# ultimatedrive1.net
KiCad netlist of a schematic drawn in EAGLE
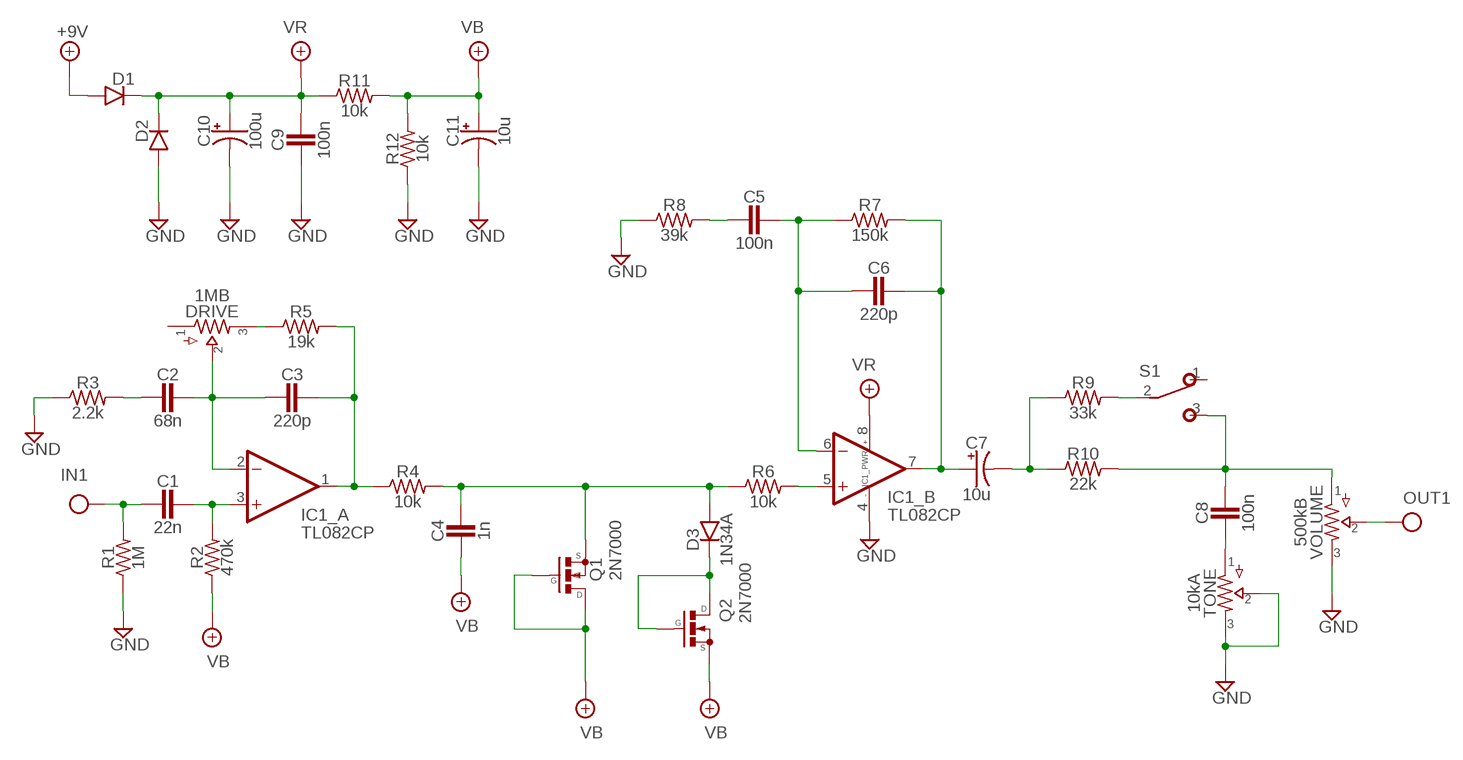
[diagram p0: schematic, sheet 1]

(export (version "E")
  (design (tool "Eeschema 10.0.6"))
  (components
    (comp (ref "C1")
      (value "22n")
      (footprint "eagle-import:BOX_SMALL")
      (libsource (lib "eagle-import") (part "CER/FILMBOX.1"))
    )
    (comp (ref "C2")
      (value "68n")
      (footprint "eagle-import:BOX_SMALL")
      (libsource (lib "eagle-import") (part "CER/FILMBOX.1"))
    )
    (comp (ref "C3")
      (value "220p")
      (footprint "eagle-import:BOX_SMALL")
      (libsource (lib "eagle-import") (part "CER/FILMBOX.1"))
    )
    (comp (ref "C4")
      (value "1n")
      (footprint "eagle-import:BOX_SMALL")
      (libsource (lib "eagle-import") (part "CER/FILMBOX.1"))
    )
    (comp (ref "C5")
      (value "100n")
      (footprint "eagle-import:BOX_SMALL")
      (libsource (lib "eagle-import") (part "CER/FILMBOX.1"))
    )
    (comp (ref "C6")
      (value "220p")
      (footprint "eagle-import:BOX_SMALL")
      (libsource (lib "eagle-import") (part "CER/FILMBOX.1"))
    )
    (comp (ref "C7")
      (value "10u")
      (footprint "eagle-import:050_020")
      (libsource (lib "eagle-import") (part "0500"))
    )
    (comp (ref "C8")
      (value "100n")
      (footprint "eagle-import:BOX_SMALL")
      (libsource (lib "eagle-import") (part "CER/FILMBOX.1"))
    )
    (comp (ref "C9")
      (value "100n")
      (footprint "eagle-import:BOX_SMALL")
      (libsource (lib "eagle-import") (part "CER/FILMBOX.1"))
    )
    (comp (ref "C10")
      (value "100u")
      (footprint "eagle-import:050_020")
      (libsource (lib "eagle-import") (part "0500"))
    )
    (comp (ref "C11")
      (value "10u")
      (footprint "eagle-import:050_020")
      (libsource (lib "eagle-import") (part "0500"))
    )
    (comp (ref "D1")
      (value "DO41.3")
      (footprint "eagle-import:DO41-3")
      (libsource (lib "eagle-import") (part "DO41.3"))
    )
    (comp (ref "D2")
      (value "DO41.3")
      (footprint "eagle-import:DO41-3")
      (libsource (lib "eagle-import") (part "DO41.3"))
    )
    (comp (ref "D3")
      (value "1N34A")
      (footprint "eagle-import:DO41-2")
      (libsource (lib "eagle-import") (part "DO41.2"))
    )
    (comp (ref "DRIVE")
      (value "1MB")
      (footprint "eagle-import:16MM")
      (libsource (lib "eagle-import") (part "POTS16MM"))
    )
    (comp (ref "IC1")
      (value "TL082CP")
      (footprint "eagle-import:DIL0")
      (libsource (lib "eagle-import") (part "DUALTH"))
    )
    (comp (ref "Q1")
      (value "2N7000")
      (footprint "eagle-import:TO92-")
      (libsource (lib "eagle-import") (part "2N7000"))
    )
    (comp (ref "Q2")
      (value "2N7000")
      (footprint "eagle-import:TO92-")
      (libsource (lib "eagle-import") (part "2N7000"))
    )
    (comp (ref "R1")
      (value "1M")
      (footprint "eagle-import:R0207_3")
      (libsource (lib "eagle-import") (part "R_.3B"))
    )
    (comp (ref "R2")
      (value "470k")
      (footprint "eagle-import:R0207_3")
      (libsource (lib "eagle-import") (part "R_.3B"))
    )
    (comp (ref "R3")
      (value "2.2k")
      (footprint "eagle-import:R0207_3")
      (libsource (lib "eagle-import") (part "R_.3B"))
    )
    (comp (ref "R4")
      (value "10k")
      (footprint "eagle-import:R0207_3")
      (libsource (lib "eagle-import") (part "R_.3B"))
    )
    (comp (ref "R5")
      (value "19k")
      (footprint "eagle-import:R0207_3")
      (libsource (lib "eagle-import") (part "R_.3B"))
    )
    (comp (ref "R6")
      (value "10k")
      (footprint "eagle-import:R0207_3")
      (libsource (lib "eagle-import") (part "R_.3B"))
    )
    (comp (ref "R7")
      (value "150k")
      (footprint "eagle-import:R0207_3")
      (libsource (lib "eagle-import") (part "R_.3B"))
    )
    (comp (ref "R8")
      (value "39k")
      (footprint "eagle-import:R0207_3")
      (libsource (lib "eagle-import") (part "R_.3B"))
    )
    (comp (ref "R9")
      (value "33k")
      (footprint "eagle-import:R0207_3")
      (libsource (lib "eagle-import") (part "R_.3B"))
    )
    (comp (ref "R10")
      (value "22k")
      (footprint "eagle-import:R0207_3")
      (libsource (lib "eagle-import") (part "R_.3B"))
    )
    (comp (ref "R11")
      (value "10k")
      (footprint "eagle-import:R0207_3")
      (libsource (lib "eagle-import") (part "R_.3B"))
    )
    (comp (ref "R12")
      (value "10k")
      (footprint "eagle-import:R0207_3")
      (libsource (lib "eagle-import") (part "R_.3B"))
    )
    (comp (ref "S1")
      (value "SPDT")
      (footprint "eagle-import:M9040P")
      (libsource (lib "eagle-import") (part "SPDT"))
    )
    (comp (ref "TONE")
      (value "10kA")
      (footprint "eagle-import:16MM")
      (libsource (lib "eagle-import") (part "POTS16MM"))
    )
    (comp (ref "VOLUME")
      (value "500kB")
      (footprint "eagle-import:16MM")
      (libsource (lib "eagle-import") (part "POTS16MM"))
    )
  )
  (nets
    (net (code "1") (name "+9V") (class "Default")
      (node (ref "D1") (pin "A") (pinfunction "A_A") (pintype "passive"))
    )
    (net (code "2") (name "GND") (class "Default")
      (node (ref "C10") (pin "-") (pinfunction "-_-") (pintype "passive"))
      (node (ref "C11") (pin "-") (pinfunction "-_-") (pintype "passive"))
      (node (ref "C9") (pin "2") (pinfunction "2_2") (pintype "passive"))
      (node (ref "D2") (pin "A") (pinfunction "A_A") (pintype "passive"))
      (node (ref "IC1") (pin "4") (pinfunction "V-_4") (pintype "power_in"))
      (node (ref "R1") (pin "1") (pinfunction "1_1") (pintype "passive"))
      (node (ref "R12") (pin "1") (pinfunction "1_1") (pintype "passive"))
      (node (ref "R3") (pin "1") (pinfunction "1_1") (pintype "passive"))
      (node (ref "R8") (pin "1") (pinfunction "1_1") (pintype "passive"))
      (node (ref "TONE") (pin "2") (pinfunction "2_2") (pintype "passive"))
      (node (ref "TONE") (pin "3") (pinfunction "3_3") (pintype "passive"))
      (node (ref "VOLUME") (pin "3") (pinfunction "3_3") (pintype "passive"))
    )
    (net (code "3") (name "IN") (class "Default")
      (node (ref "C1") (pin "2") (pinfunction "2_2") (pintype "passive"))
      (node (ref "R1") (pin "2") (pinfunction "2_2") (pintype "passive"))
    )
    (net (code "4") (name "Net-(C2-Pad2)") (class "Default")
      (node (ref "C2") (pin "2") (pinfunction "2_2") (pintype "passive"))
      (node (ref "R3") (pin "2") (pinfunction "2_2") (pintype "passive"))
    )
    (net (code "5") (name "Net-(C5-Pad2)") (class "Default")
      (node (ref "C5") (pin "2") (pinfunction "2_2") (pintype "passive"))
      (node (ref "R8") (pin "2") (pinfunction "2_2") (pintype "passive"))
    )
    (net (code "6") (name "Net-(C7-Pad-)") (class "Default")
      (node (ref "C7") (pin "-") (pinfunction "-_-") (pintype "passive"))
      (node (ref "R10") (pin "1") (pinfunction "1_1") (pintype "passive"))
      (node (ref "R9") (pin "1") (pinfunction "1_1") (pintype "passive"))
    )
    (net (code "7") (name "Net-(C8-Pad2)") (class "Default")
      (node (ref "C8") (pin "2") (pinfunction "2_2") (pintype "passive"))
      (node (ref "TONE") (pin "1") (pinfunction "1_1") (pintype "passive"))
    )
    (net (code "8") (name "Net-(DRIVE-Pad3)") (class "Default")
      (node (ref "DRIVE") (pin "3") (pinfunction "3_3") (pintype "passive"))
      (node (ref "R5") (pin "1") (pinfunction "1_1") (pintype "passive"))
    )
    (net (code "9") (name "Net-(IC1A-+IN)") (class "Default")
      (node (ref "C1") (pin "1") (pinfunction "1_1") (pintype "passive"))
      (node (ref "IC1") (pin "3") (pinfunction "+IN_3") (pintype "input"))
      (node (ref "R2") (pin "2") (pinfunction "2_2") (pintype "passive"))
    )
    (net (code "10") (name "Net-(IC1A--IN)") (class "Default")
      (node (ref "C2") (pin "1") (pinfunction "1_1") (pintype "passive"))
      (node (ref "C3") (pin "2") (pinfunction "2_2") (pintype "passive"))
      (node (ref "DRIVE") (pin "2") (pinfunction "2_2") (pintype "passive"))
      (node (ref "IC1") (pin "2") (pinfunction "-IN_2") (pintype "input"))
    )
    (net (code "11") (name "Net-(IC1A-OUT)") (class "Default")
      (node (ref "C3") (pin "1") (pinfunction "1_1") (pintype "passive"))
      (node (ref "IC1") (pin "1") (pinfunction "OUT_1") (pintype "output"))
      (node (ref "R4") (pin "1") (pinfunction "1_1") (pintype "passive"))
      (node (ref "R5") (pin "2") (pinfunction "2_2") (pintype "passive"))
    )
    (net (code "12") (name "Net-(IC1B-+IN)") (class "Default")
      (node (ref "IC1") (pin "5") (pinfunction "+IN_5") (pintype "input"))
      (node (ref "R6") (pin "2") (pinfunction "2_2") (pintype "passive"))
    )
    (net (code "13") (name "Net-(IC1B--IN)") (class "Default")
      (node (ref "C5") (pin "1") (pinfunction "1_1") (pintype "passive"))
      (node (ref "C6") (pin "2") (pinfunction "2_2") (pintype "passive"))
      (node (ref "IC1") (pin "6") (pinfunction "-IN_6") (pintype "input"))
      (node (ref "R7") (pin "1") (pinfunction "1_1") (pintype "passive"))
    )
    (net (code "14") (name "Net-(IC1B-OUT)") (class "Default")
      (node (ref "C6") (pin "1") (pinfunction "1_1") (pintype "passive"))
      (node (ref "C7") (pin "+") (pinfunction "+_+") (pintype "passive"))
      (node (ref "IC1") (pin "7") (pinfunction "OUT_7") (pintype "output"))
      (node (ref "R7") (pin "2") (pinfunction "2_2") (pintype "passive"))
    )
    (net (code "15") (name "Net-(Q1-S)") (class "Default")
      (node (ref "C4") (pin "1") (pinfunction "1_1") (pintype "passive"))
      (node (ref "D3") (pin "A") (pinfunction "A_A") (pintype "passive"))
      (node (ref "Q1") (pin "3") (pinfunction "S_3") (pintype "passive"))
      (node (ref "R4") (pin "2") (pinfunction "2_2") (pintype "passive"))
      (node (ref "R6") (pin "1") (pinfunction "1_1") (pintype "passive"))
    )
    (net (code "16") (name "Net-(Q2-D)") (class "Default")
      (node (ref "D3") (pin "C") (pinfunction "C_C") (pintype "passive"))
      (node (ref "Q2") (pin "1") (pinfunction "D_1") (pintype "passive"))
      (node (ref "Q2") (pin "2") (pinfunction "G_2") (pintype "passive"))
    )
    (net (code "17") (name "Net-(S1-P)") (class "Default")
      (node (ref "R9") (pin "2") (pinfunction "2_2") (pintype "passive"))
      (node (ref "S1") (pin "2") (pinfunction "P_2") (pintype "passive"))
    )
    (net (code "18") (name "Net-(S1-S)") (class "Default")
      (node (ref "C8") (pin "1") (pinfunction "1_1") (pintype "passive"))
      (node (ref "R10") (pin "2") (pinfunction "2_2") (pintype "passive"))
      (node (ref "S1") (pin "3") (pinfunction "S_3") (pintype "passive"))
      (node (ref "VOLUME") (pin "1") (pinfunction "1_1") (pintype "passive"))
    )
    (net (code "19") (name "OUT") (class "Default")
      (node (ref "VOLUME") (pin "2") (pinfunction "2_2") (pintype "passive"))
    )
    (net (code "20") (name "VB") (class "Default")
      (node (ref "C11") (pin "+") (pinfunction "+_+") (pintype "passive"))
      (node (ref "C4") (pin "2") (pinfunction "2_2") (pintype "passive"))
      (node (ref "Q1") (pin "1") (pinfunction "D_1") (pintype "passive"))
      (node (ref "Q1") (pin "2") (pinfunction "G_2") (pintype "passive"))
      (node (ref "Q2") (pin "3") (pinfunction "S_3") (pintype "passive"))
      (node (ref "R11") (pin "2") (pinfunction "2_2") (pintype "passive"))
      (node (ref "R12") (pin "2") (pinfunction "2_2") (pintype "passive"))
      (node (ref "R2") (pin "1") (pinfunction "1_1") (pintype "passive"))
    )
    (net (code "21") (name "VR") (class "Default")
      (node (ref "C10") (pin "+") (pinfunction "+_+") (pintype "passive"))
      (node (ref "C9") (pin "1") (pinfunction "1_1") (pintype "passive"))
      (node (ref "D1") (pin "C") (pinfunction "C_C") (pintype "passive"))
      (node (ref "D2") (pin "C") (pinfunction "C_C") (pintype "passive"))
      (node (ref "IC1") (pin "8") (pinfunction "V+_8") (pintype "power_in"))
      (node (ref "R11") (pin "1") (pinfunction "1_1") (pintype "passive"))
    )
    (net (code "22") (name "unconnected-(DRIVE-Pad1)") (class "Default")
      (node (ref "DRIVE") (pin "1") (pinfunction "1_1") (pintype "passive"))
    )
    (net (code "23") (name "unconnected-(S1-O-Pad1)") (class "Default")
      (node (ref "S1") (pin "1") (pinfunction "O_1") (pintype "passive"))
    )
  )
)
